# untitled_front4.net
KiCad netlist of a schematic drawn in EAGLE
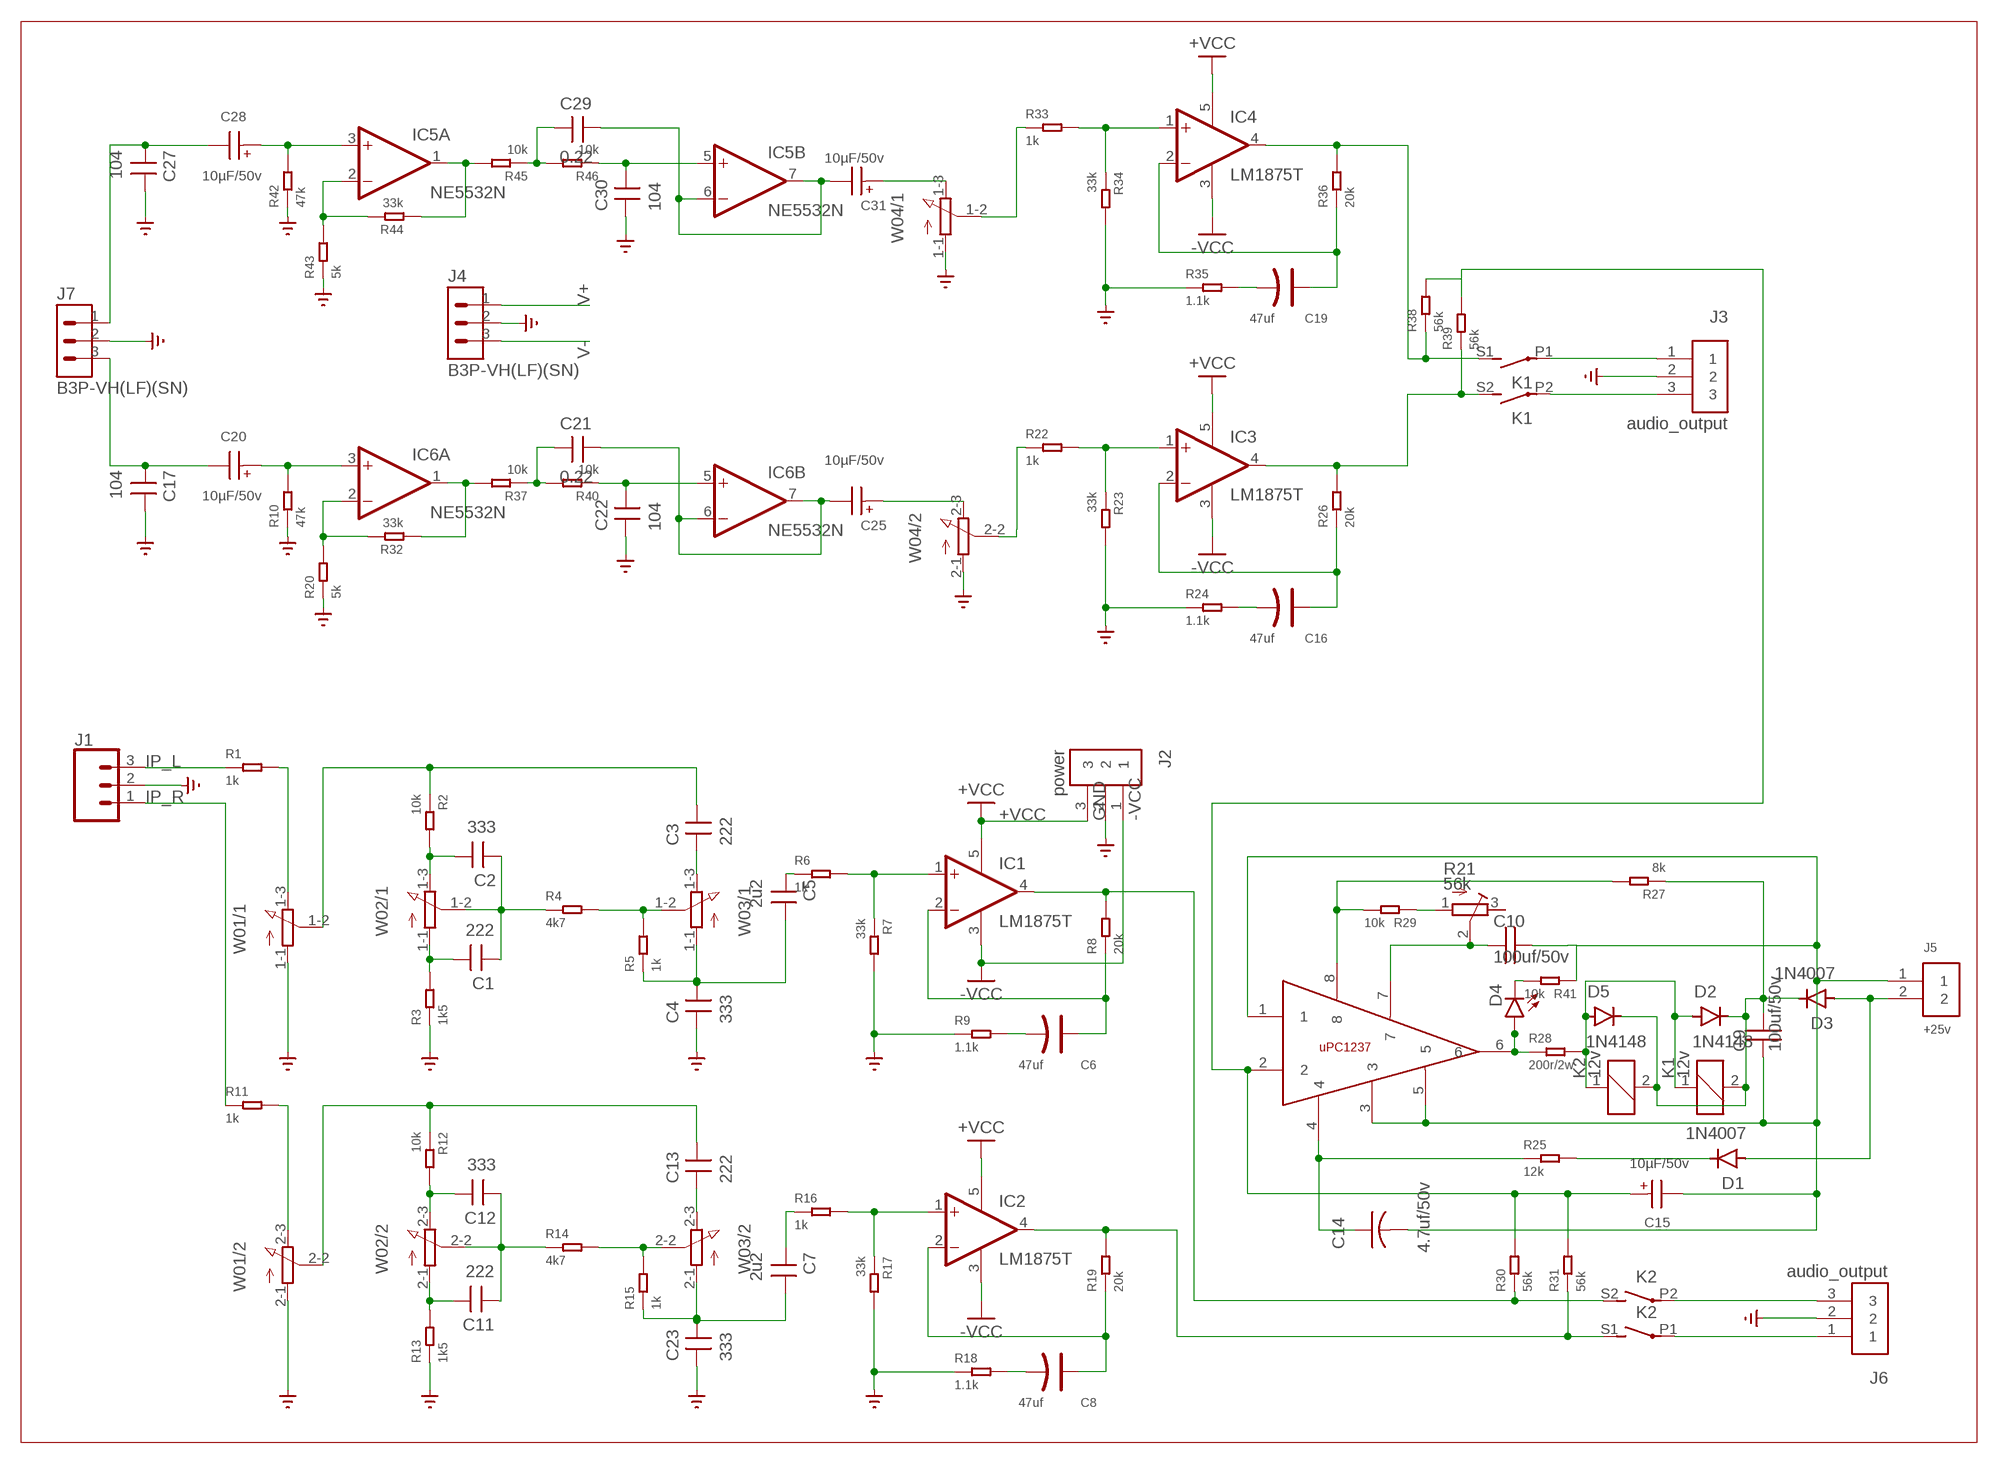
[diagram p0: schematic, sheet 1]

(export (version "E")
  (design (tool "Eeschema 10.0.6"))
  (components
    (comp (ref "C1")
      (value "222")
      (footprint "eagle-import:5.08MM-独石电容")
      (libsource (lib "eagle-import") (part "5.08MM-"))
    )
    (comp (ref "C2")
      (value "333")
      (footprint "eagle-import:5.08MM-独石电容")
      (libsource (lib "eagle-import") (part "5.08MM-"))
    )
    (comp (ref "C3")
      (value "222")
      (footprint "eagle-import:5.08MM-独石电容")
      (libsource (lib "eagle-import") (part "5.08MM-"))
    )
    (comp (ref "C4")
      (value "333")
      (footprint "eagle-import:5.08MM-独石电容")
      (libsource (lib "eagle-import") (part "5.08MM-"))
    )
    (comp (ref "C5")
      (value "2u2")
      (footprint "eagle-import:5.08MM-独石电容")
      (libsource (lib "eagle-import") (part "5.08MM-"))
    )
    (comp (ref "C6")
      (value "47uf")
      (footprint "eagle-import:PC-D5.3MM")
      (fields (field (name "MPN") "KS 100uF/16V"))
      (libsource (lib "eagle-import") (part "DIP-ALUMINUM-47UF-16V(D5-H7MM)"))
    )
    (comp (ref "C7")
      (value "2u2")
      (footprint "eagle-import:5.08MM-独石电容")
      (libsource (lib "eagle-import") (part "5.08MM-"))
    )
    (comp (ref "C8")
      (value "47uf")
      (footprint "eagle-import:PC-D5.3MM")
      (fields (field (name "MPN") "KS 100uF/16V"))
      (libsource (lib "eagle-import") (part "DIP-ALUMINUM-47UF-16V(D5-H7MM)"))
    )
    (comp (ref "C9")
      (value "100uf/50v")
      (footprint "eagle-import:8X12")
      (libsource (lib "eagle-import") (part "50V100UF8X12"))
    )
    (comp (ref "C10")
      (value "100uf/50v")
      (footprint "eagle-import:8X12")
      (libsource (lib "eagle-import") (part "50V100UF8X12"))
    )
    (comp (ref "C11")
      (value "222")
      (footprint "eagle-import:5.08MM-独石电容")
      (libsource (lib "eagle-import") (part "5.08MM-"))
    )
    (comp (ref "C12")
      (value "333")
      (footprint "eagle-import:5.08MM-独石电容")
      (libsource (lib "eagle-import") (part "5.08MM-"))
    )
    (comp (ref "C13")
      (value "222")
      (footprint "eagle-import:5.08MM-独石电容")
      (libsource (lib "eagle-import") (part "5.08MM-"))
    )
    (comp (ref "C14")
      (value "4.7uf/50v")
      (footprint "eagle-import:CAP_RADIAL_2MM")
      (fields
        (field (name "DIGIKEY_PART_NUMBER") "P5175-ND")
        (field (name "MANUFACTURER") "Panasonic Electronic Components")
        (field (name "MPN") "ECA-1HM2R2")
        (field (name "CREATED_BY") "PCBLayout.com")
      )
      (libsource (lib "eagle-import") (part "ECA-1HM2R2"))
    )
    (comp (ref "C15")
      (value "10µF/50v")
      (footprint "eagle-import:WCAP-AT1H_5X11(DXL)")
      (libsource (lib "eagle-import") (part "WCAP-AT1H_5X11_860240272001"))
    )
    (comp (ref "C16")
      (value "47uf")
      (footprint "eagle-import:PC-D5.3MM")
      (fields (field (name "MPN") "KS 100uF/16V"))
      (libsource (lib "eagle-import") (part "DIP-ALUMINUM-47UF-16V(D5-H7MM)"))
    )
    (comp (ref "C17")
      (value "104")
      (footprint "eagle-import:5.08MM-独石电容")
      (libsource (lib "eagle-import") (part "5.08MM-"))
    )
    (comp (ref "C19")
      (value "47uf")
      (footprint "eagle-import:PC-D5.3MM")
      (fields (field (name "MPN") "KS 100uF/16V"))
      (libsource (lib "eagle-import") (part "DIP-ALUMINUM-47UF-16V(D5-H7MM)"))
    )
    (comp (ref "C20")
      (value "10µF/50v")
      (footprint "eagle-import:WCAP-AT1H_5X11(DXL)")
      (libsource (lib "eagle-import") (part "WCAP-AT1H_5X11_860240272001"))
    )
    (comp (ref "C21")
      (value "0.22")
      (footprint "eagle-import:5.08MM-独石电容")
      (libsource (lib "eagle-import") (part "5.08MM-"))
    )
    (comp (ref "C22")
      (value "104")
      (footprint "eagle-import:5.08MM-独石电容")
      (libsource (lib "eagle-import") (part "5.08MM-"))
    )
    (comp (ref "C23")
      (value "333")
      (footprint "eagle-import:5.08MM-独石电容")
      (libsource (lib "eagle-import") (part "5.08MM-"))
    )
    (comp (ref "C25")
      (value "10µF/50v")
      (footprint "eagle-import:WCAP-AT1H_5X11(DXL)")
      (libsource (lib "eagle-import") (part "WCAP-AT1H_5X11_860240272001"))
    )
    (comp (ref "C27")
      (value "104")
      (footprint "eagle-import:5.08MM-独石电容")
      (libsource (lib "eagle-import") (part "5.08MM-"))
    )
    (comp (ref "C28")
      (value "10µF/50v")
      (footprint "eagle-import:WCAP-AT1H_5X11(DXL)")
      (libsource (lib "eagle-import") (part "WCAP-AT1H_5X11_860240272001"))
    )
    (comp (ref "C29")
      (value "0.22")
      (footprint "eagle-import:5.08MM-独石电容")
      (libsource (lib "eagle-import") (part "5.08MM-"))
    )
    (comp (ref "C30")
      (value "104")
      (footprint "eagle-import:5.08MM-独石电容")
      (libsource (lib "eagle-import") (part "5.08MM-"))
    )
    (comp (ref "C31")
      (value "10µF/50v")
      (footprint "eagle-import:WCAP-AT1H_5X11(DXL)")
      (libsource (lib "eagle-import") (part "WCAP-AT1H_5X11_860240272001"))
    )
    (comp (ref "D1")
      (value "1N4007")
      (footprint "eagle-import:DO-41")
      (fields
        (field (name "DIGIKEY_PART_NUMBER") "1N4007MSCT-ND")
        (field (name "MANUFACTURER") "Micro Commercial Co")
        (field (name "CREATED_BY") "PCBLayout.com")
      )
      (libsource (lib "eagle-import") (part "1N4007"))
    )
    (comp (ref "D2")
      (value "1N4148")
      (footprint "eagle-import:DO-41")
      (fields
        (field (name "DIGIKEY_PART_NUMBER") "1N4007MSCT-ND")
        (field (name "MANUFACTURER") "Micro Commercial Co")
        (field (name "MPN") "1N4007")
        (field (name "CREATED_BY") "PCBLayout.com")
      )
      (libsource (lib "eagle-import") (part "1N4007"))
    )
    (comp (ref "D3")
      (value "1N4007")
      (footprint "eagle-import:DO-41")
      (fields
        (field (name "DIGIKEY_PART_NUMBER") "1N4007MSCT-ND")
        (field (name "MANUFACTURER") "Micro Commercial Co")
        (field (name "CREATED_BY") "PCBLayout.com")
      )
      (libsource (lib "eagle-import") (part "1N4007"))
    )
    (comp (ref "D4")
      (value "BEAGLEBONE_BLUE_LED-3MM-NO_SILK")
      (footprint "eagle-import:BEAGLEBONE_BLUE_BEAGLEBONE_BLUE_LED3MM-NS")
      (libsource (lib "eagle-import") (part "BEAGLEBONE_BLUE_LED-3MM-NO_SILK"))
    )
    (comp (ref "D5")
      (value "1N4148")
      (footprint "eagle-import:DO-41")
      (fields
        (field (name "DIGIKEY_PART_NUMBER") "1N4007MSCT-ND")
        (field (name "MANUFACTURER") "Micro Commercial Co")
        (field (name "MPN") "1N4007")
        (field (name "CREATED_BY") "PCBLayout.com")
      )
      (libsource (lib "eagle-import") (part "1N4007"))
    )
    (comp (ref "IC1")
      (value "LM1875T")
      (footprint "eagle-import:CB367")
      (libsource (lib "eagle-import") (part "LM1875T"))
    )
    (comp (ref "IC2")
      (value "LM1875T")
      (footprint "eagle-import:CB367")
      (libsource (lib "eagle-import") (part "LM1875T"))
    )
    (comp (ref "IC3")
      (value "LM1875T")
      (footprint "eagle-import:CB367")
      (libsource (lib "eagle-import") (part "LM1875T"))
    )
    (comp (ref "IC4")
      (value "LM1875T")
      (footprint "eagle-import:CB367")
      (libsource (lib "eagle-import") (part "LM1875T"))
    )
    (comp (ref "IC5")
      (value "NE5532N")
      (footprint "eagle-import:DIL08")
      (libsource (lib "eagle-import") (part "NE5532N"))
    )
    (comp (ref "IC6")
      (value "NE5532N")
      (footprint "eagle-import:DIL08")
      (libsource (lib "eagle-import") (part "NE5532N"))
    )
    (comp (ref "J1")
      (value "CONN_03POLAR")
      (footprint "eagle-import:MOLEX-1X3")
      (libsource (lib "eagle-import") (part "CONN_03POLAR"))
    )
    (comp (ref "J2")
      (value "power")
      (footprint "eagle-import:TERMINALBLOCK_PLUGGABLE-3-7.62MM")
      (fields
        (field (name "DIGIKEY_PART_NO") "732-2824-ND")
        (field (name "MANUFACTURER") "WURTH ELEKTRONIK")
        (field (name "MPN") "691311400103")
        (field (name "CREATED_BY") "PCBLayout.com")
      )
      (libsource (lib "eagle-import") (part "691311400103"))
    )
    (comp (ref "J3")
      (value "audio_output")
      (footprint "eagle-import:TERMINALBLOCK_PLUGGABLE-3-7.62MM")
      (fields
        (field (name "DIGIKEY_PART_NO") "732-2824-ND")
        (field (name "MANUFACTURER") "WURTH ELEKTRONIK")
        (field (name "MPN") "691311400103")
        (field (name "CREATED_BY") "PCBLayout.com")
      )
      (libsource (lib "eagle-import") (part "691311400103"))
    )
    (comp (ref "J4")
      (value "B3P-VH(LF)(SN)")
      (footprint "eagle-import:HDR-03")
      (fields
        (field (name "DIGIKEY_PART_NUMBER") "455-1640-ND")
        (field (name "MANUFACTURER") "JST Sales America Inc.")
        (field (name "CREATED_BY") "PCBLayout.com")
      )
      (libsource (lib "eagle-import") (part "B3P-VH(LF)(SN)"))
    )
    (comp (ref "J5")
      (value "+25v")
      (footprint "eagle-import:S2B-PH-K-S(LF)(SN)")
      (fields
        (field (name "DIGI_KEY_PART_NUMBER") "455-1719-ND")
        (field (name "MANUFACTURER") "JST Sales America Inc.")
        (field (name "MPN") "S2B-PH-K-S(LF)(SN)")
        (field (name "CREATED_BY") "PCBLayout.com")
      )
      (libsource (lib "eagle-import") (part "S2B-PH-K-S(LF)(SN)"))
    )
    (comp (ref "J6")
      (value "audio_output")
      (footprint "eagle-import:TERMINALBLOCK_PLUGGABLE-3-7.62MM")
      (fields
        (field (name "DIGIKEY_PART_NO") "732-2824-ND")
        (field (name "MANUFACTURER") "WURTH ELEKTRONIK")
        (field (name "MPN") "691311400103")
        (field (name "CREATED_BY") "PCBLayout.com")
      )
      (libsource (lib "eagle-import") (part "691311400103"))
    )
    (comp (ref "J7")
      (value "B3P-VH(LF)(SN)")
      (footprint "eagle-import:HDR-03")
      (fields
        (field (name "DIGIKEY_PART_NUMBER") "455-1640-ND")
        (field (name "MANUFACTURER") "JST Sales America Inc.")
        (field (name "CREATED_BY") "PCBLayout.com")
      )
      (libsource (lib "eagle-import") (part "B3P-VH(LF)(SN)"))
    )
    (comp (ref "K1")
      (value "12v")
      (footprint "eagle-import:G2R2A")
      (fields (field (name "MPN") "G2R-2A-DC24"))
      (libsource (lib "eagle-import") (part "G2R2A"))
    )
    (comp (ref "K2")
      (value "12v")
      (footprint "eagle-import:G2R2A")
      (fields (field (name "MPN") "G2R-2A-DC24"))
      (libsource (lib "eagle-import") (part "G2R2A"))
    )
    (comp (ref "R1")
      (value "1k")
      (footprint "eagle-import:PR-D2.3XL6.5MM")
      (fields (field (name "MPN") "FHCFR-1/4W-105J"))
      (libsource (lib "eagle-import") (part "DIP-RES-1M-5%-1/4W(PR-D2.3XL6.5MM)"))
    )
    (comp (ref "R2")
      (value "10k")
      (footprint "eagle-import:PR-D2.3XL6.5MM")
      (fields (field (name "MPN") "FHCFR-1/4W-105J"))
      (libsource (lib "eagle-import") (part "DIP-RES-1M-5%-1/4W(PR-D2.3XL6.5MM)"))
    )
    (comp (ref "R3")
      (value "1k5")
      (footprint "eagle-import:PR-D2.3XL6.5MM")
      (fields (field (name "MPN") "FHCFR-1/4W-105J"))
      (libsource (lib "eagle-import") (part "DIP-RES-1M-5%-1/4W(PR-D2.3XL6.5MM)"))
    )
    (comp (ref "R4")
      (value "4k7")
      (footprint "eagle-import:PR-D2.3XL6.5MM")
      (fields (field (name "MPN") "FHCFR-1/4W-105J"))
      (libsource (lib "eagle-import") (part "DIP-RES-1M-5%-1/4W(PR-D2.3XL6.5MM)"))
    )
    (comp (ref "R5")
      (value "1k")
      (footprint "eagle-import:PR-D2.3XL6.5MM")
      (fields (field (name "MPN") "FHCFR-1/4W-105J"))
      (libsource (lib "eagle-import") (part "DIP-RES-1M-5%-1/4W(PR-D2.3XL6.5MM)"))
    )
    (comp (ref "R6")
      (value "1k")
      (footprint "eagle-import:PR-D2.3XL6.5MM")
      (fields (field (name "MPN") "FHCFR-1/4W-105J"))
      (libsource (lib "eagle-import") (part "DIP-RES-1M-5%-1/4W(PR-D2.3XL6.5MM)"))
    )
    (comp (ref "R7")
      (value "33k")
      (footprint "eagle-import:PR-D2.3XL6.5MM")
      (fields (field (name "MPN") "FHCFR-1/4W-105J"))
      (libsource (lib "eagle-import") (part "DIP-RES-1M-5%-1/4W(PR-D2.3XL6.5MM)"))
    )
    (comp (ref "R8")
      (value "20k")
      (footprint "eagle-import:PR-D2.3XL6.5MM")
      (fields (field (name "MPN") "FHCFR-1/4W-105J"))
      (libsource (lib "eagle-import") (part "DIP-RES-1M-5%-1/4W(PR-D2.3XL6.5MM)"))
    )
    (comp (ref "R9")
      (value "1.1k")
      (footprint "eagle-import:PR-D2.3XL6.5MM")
      (fields (field (name "MPN") "FHCFR-1/4W-105J"))
      (libsource (lib "eagle-import") (part "DIP-RES-1M-5%-1/4W(PR-D2.3XL6.5MM)"))
    )
    (comp (ref "R10")
      (value "47k")
      (footprint "eagle-import:PR-D2.3XL6.5MM")
      (fields (field (name "MPN") "FHCFR-1/4W-105J"))
      (libsource (lib "eagle-import") (part "DIP-RES-1M-5%-1/4W(PR-D2.3XL6.5MM)"))
    )
    (comp (ref "R11")
      (value "1k")
      (footprint "eagle-import:PR-D2.3XL6.5MM")
      (fields (field (name "MPN") "FHCFR-1/4W-105J"))
      (libsource (lib "eagle-import") (part "DIP-RES-1M-5%-1/4W(PR-D2.3XL6.5MM)"))
    )
    (comp (ref "R12")
      (value "10k")
      (footprint "eagle-import:PR-D2.3XL6.5MM")
      (fields (field (name "MPN") "FHCFR-1/4W-105J"))
      (libsource (lib "eagle-import") (part "DIP-RES-1M-5%-1/4W(PR-D2.3XL6.5MM)"))
    )
    (comp (ref "R13")
      (value "1k5")
      (footprint "eagle-import:PR-D2.3XL6.5MM")
      (fields (field (name "MPN") "FHCFR-1/4W-105J"))
      (libsource (lib "eagle-import") (part "DIP-RES-1M-5%-1/4W(PR-D2.3XL6.5MM)"))
    )
    (comp (ref "R14")
      (value "4k7")
      (footprint "eagle-import:PR-D2.3XL6.5MM")
      (fields (field (name "MPN") "FHCFR-1/4W-105J"))
      (libsource (lib "eagle-import") (part "DIP-RES-1M-5%-1/4W(PR-D2.3XL6.5MM)"))
    )
    (comp (ref "R15")
      (value "1k")
      (footprint "eagle-import:PR-D2.3XL6.5MM")
      (fields (field (name "MPN") "FHCFR-1/4W-105J"))
      (libsource (lib "eagle-import") (part "DIP-RES-1M-5%-1/4W(PR-D2.3XL6.5MM)"))
    )
    (comp (ref "R16")
      (value "1k")
      (footprint "eagle-import:PR-D2.3XL6.5MM")
      (fields (field (name "MPN") "FHCFR-1/4W-105J"))
      (libsource (lib "eagle-import") (part "DIP-RES-1M-5%-1/4W(PR-D2.3XL6.5MM)"))
    )
    (comp (ref "R17")
      (value "33k")
      (footprint "eagle-import:PR-D2.3XL6.5MM")
      (fields (field (name "MPN") "FHCFR-1/4W-105J"))
      (libsource (lib "eagle-import") (part "DIP-RES-1M-5%-1/4W(PR-D2.3XL6.5MM)"))
    )
    (comp (ref "R18")
      (value "1.1k")
      (footprint "eagle-import:PR-D2.3XL6.5MM")
      (fields (field (name "MPN") "FHCFR-1/4W-105J"))
      (libsource (lib "eagle-import") (part "DIP-RES-1M-5%-1/4W(PR-D2.3XL6.5MM)"))
    )
    (comp (ref "R19")
      (value "20k")
      (footprint "eagle-import:PR-D2.3XL6.5MM")
      (fields (field (name "MPN") "FHCFR-1/4W-105J"))
      (libsource (lib "eagle-import") (part "DIP-RES-1M-5%-1/4W(PR-D2.3XL6.5MM)"))
    )
    (comp (ref "R20")
      (value "5k")
      (footprint "eagle-import:PR-D2.3XL6.5MM")
      (fields (field (name "MPN") "FHCFR-1/4W-105J"))
      (libsource (lib "eagle-import") (part "DIP-RES-1M-5%-1/4W(PR-D2.3XL6.5MM)"))
    )
    (comp (ref "R21")
      (value "56k")
      (footprint "eagle-import:RTRIM3296W")
      (libsource (lib "eagle-import") (part "R-TRIMM3296W"))
    )
    (comp (ref "R22")
      (value "1k")
      (footprint "eagle-import:PR-D2.3XL6.5MM")
      (fields (field (name "MPN") "FHCFR-1/4W-105J"))
      (libsource (lib "eagle-import") (part "DIP-RES-1M-5%-1/4W(PR-D2.3XL6.5MM)"))
    )
    (comp (ref "R23")
      (value "33k")
      (footprint "eagle-import:PR-D2.3XL6.5MM")
      (fields (field (name "MPN") "FHCFR-1/4W-105J"))
      (libsource (lib "eagle-import") (part "DIP-RES-1M-5%-1/4W(PR-D2.3XL6.5MM)"))
    )
    (comp (ref "R24")
      (value "1.1k")
      (footprint "eagle-import:PR-D2.3XL6.5MM")
      (fields (field (name "MPN") "FHCFR-1/4W-105J"))
      (libsource (lib "eagle-import") (part "DIP-RES-1M-5%-1/4W(PR-D2.3XL6.5MM)"))
    )
    (comp (ref "R25")
      (value "12k")
      (footprint "eagle-import:PR-D2.3XL6.5MM")
      (fields (field (name "MPN") "FHCFR-1/4W-105J"))
      (libsource (lib "eagle-import") (part "DIP-RES-1M-5%-1/4W(PR-D2.3XL6.5MM)"))
    )
    (comp (ref "R26")
      (value "20k")
      (footprint "eagle-import:PR-D2.3XL6.5MM")
      (fields (field (name "MPN") "FHCFR-1/4W-105J"))
      (libsource (lib "eagle-import") (part "DIP-RES-1M-5%-1/4W(PR-D2.3XL6.5MM)"))
    )
    (comp (ref "R27")
      (value "8k")
      (footprint "eagle-import:PR-D2.3XL6.5MM")
      (fields (field (name "MPN") "FHCFR-1/4W-105J"))
      (libsource (lib "eagle-import") (part "DIP-RES-1M-5%-1/4W(PR-D2.3XL6.5MM)"))
    )
    (comp (ref "R28")
      (value "200r/2w")
      (footprint "eagle-import:PR-D2.3XL6.5MM")
      (fields (field (name "MPN") "FHCFR-1/4W-105J"))
      (libsource (lib "eagle-import") (part "DIP-RES-1M-5%-1/4W(PR-D2.3XL6.5MM)"))
    )
    (comp (ref "R29")
      (value "10k")
      (footprint "eagle-import:PR-D2.3XL6.5MM")
      (fields (field (name "MPN") "FHCFR-1/4W-105J"))
      (libsource (lib "eagle-import") (part "DIP-RES-1M-5%-1/4W(PR-D2.3XL6.5MM)"))
    )
    (comp (ref "R30")
      (value "56k")
      (footprint "eagle-import:PR-D2.3XL6.5MM")
      (fields (field (name "MPN") "FHCFR-1/4W-105J"))
      (libsource (lib "eagle-import") (part "DIP-RES-1M-5%-1/4W(PR-D2.3XL6.5MM)"))
    )
    (comp (ref "R31")
      (value "56k")
      (footprint "eagle-import:PR-D2.3XL6.5MM")
      (fields (field (name "MPN") "FHCFR-1/4W-105J"))
      (libsource (lib "eagle-import") (part "DIP-RES-1M-5%-1/4W(PR-D2.3XL6.5MM)"))
    )
    (comp (ref "R32")
      (value "33k")
      (footprint "eagle-import:PR-D2.3XL6.5MM")
      (fields (field (name "MPN") "FHCFR-1/4W-105J"))
      (libsource (lib "eagle-import") (part "DIP-RES-1M-5%-1/4W(PR-D2.3XL6.5MM)"))
    )
    (comp (ref "R33")
      (value "1k")
      (footprint "eagle-import:PR-D2.3XL6.5MM")
      (fields (field (name "MPN") "FHCFR-1/4W-105J"))
      (libsource (lib "eagle-import") (part "DIP-RES-1M-5%-1/4W(PR-D2.3XL6.5MM)"))
    )
    (comp (ref "R34")
      (value "33k")
      (footprint "eagle-import:PR-D2.3XL6.5MM")
      (fields (field (name "MPN") "FHCFR-1/4W-105J"))
      (libsource (lib "eagle-import") (part "DIP-RES-1M-5%-1/4W(PR-D2.3XL6.5MM)"))
    )
    (comp (ref "R35")
      (value "1.1k")
      (footprint "eagle-import:PR-D2.3XL6.5MM")
      (fields (field (name "MPN") "FHCFR-1/4W-105J"))
      (libsource (lib "eagle-import") (part "DIP-RES-1M-5%-1/4W(PR-D2.3XL6.5MM)"))
    )
    (comp (ref "R36")
      (value "20k")
      (footprint "eagle-import:PR-D2.3XL6.5MM")
      (fields (field (name "MPN") "FHCFR-1/4W-105J"))
      (libsource (lib "eagle-import") (part "DIP-RES-1M-5%-1/4W(PR-D2.3XL6.5MM)"))
    )
    (comp (ref "R37")
      (value "10k")
      (footprint "eagle-import:PR-D2.3XL6.5MM")
      (fields (field (name "MPN") "FHCFR-1/4W-105J"))
      (libsource (lib "eagle-import") (part "DIP-RES-1M-5%-1/4W(PR-D2.3XL6.5MM)"))
    )
    (comp (ref "R38")
      (value "56k")
      (footprint "eagle-import:PR-D2.3XL6.5MM")
      (fields (field (name "MPN") "FHCFR-1/4W-105J"))
      (libsource (lib "eagle-import") (part "DIP-RES-1M-5%-1/4W(PR-D2.3XL6.5MM)"))
    )
    (comp (ref "R39")
      (value "56k")
      (footprint "eagle-import:PR-D2.3XL6.5MM")
      (fields (field (name "MPN") "FHCFR-1/4W-105J"))
      (libsource (lib "eagle-import") (part "DIP-RES-1M-5%-1/4W(PR-D2.3XL6.5MM)"))
    )
    (comp (ref "R40")
      (value "10k")
      (footprint "eagle-import:PR-D2.3XL6.5MM")
      (fields (field (name "MPN") "FHCFR-1/4W-105J"))
      (libsource (lib "eagle-import") (part "DIP-RES-1M-5%-1/4W(PR-D2.3XL6.5MM)"))
    )
    (comp (ref "R41")
      (value "10k")
      (footprint "eagle-import:PR-D2.3XL6.5MM")
      (fields (field (name "MPN") "FHCFR-1/4W-105J"))
      (libsource (lib "eagle-import") (part "DIP-RES-1M-5%-1/4W(PR-D2.3XL6.5MM)"))
    )
    (comp (ref "R42")
      (value "47k")
      (footprint "eagle-import:PR-D2.3XL6.5MM")
      (fields (field (name "MPN") "FHCFR-1/4W-105J"))
      (libsource (lib "eagle-import") (part "DIP-RES-1M-5%-1/4W(PR-D2.3XL6.5MM)"))
    )
    (comp (ref "R43")
      (value "5k")
      (footprint "eagle-import:PR-D2.3XL6.5MM")
      (fields (field (name "MPN") "FHCFR-1/4W-105J"))
      (libsource (lib "eagle-import") (part "DIP-RES-1M-5%-1/4W(PR-D2.3XL6.5MM)"))
    )
    (comp (ref "R44")
      (value "33k")
      (footprint "eagle-import:PR-D2.3XL6.5MM")
      (fields (field (name "MPN") "FHCFR-1/4W-105J"))
      (libsource (lib "eagle-import") (part "DIP-RES-1M-5%-1/4W(PR-D2.3XL6.5MM)"))
    )
    (comp (ref "R45")
      (value "10k")
      (footprint "eagle-import:PR-D2.3XL6.5MM")
      (fields (field (name "MPN") "FHCFR-1/4W-105J"))
      (libsource (lib "eagle-import") (part "DIP-RES-1M-5%-1/4W(PR-D2.3XL6.5MM)"))
    )
    (comp (ref "R46")
      (value "10k")
      (footprint "eagle-import:PR-D2.3XL6.5MM")
      (fields (field (name "MPN") "FHCFR-1/4W-105J"))
      (libsource (lib "eagle-import") (part "DIP-RES-1M-5%-1/4W(PR-D2.3XL6.5MM)"))
    )
    (comp (ref "U2")
      (value "UPC1237HA")
      (footprint "eagle-import:SIP8")
      (libsource (lib "eagle-import") (part "UPC1237HA"))
    )
    (comp (ref "W01")
      (value "3RP/1610G")
      (footprint "eagle-import:3RP_1610G")
      (libsource (lib "eagle-import") (part "3RP/1610G"))
    )
    (comp (ref "W02")
      (value "3RP/1610G")
      (footprint "eagle-import:3RP_1610G")
      (libsource (lib "eagle-import") (part "3RP/1610G"))
    )
    (comp (ref "W03")
      (value "3RP/1610G")
      (footprint "eagle-import:3RP_1610G")
      (libsource (lib "eagle-import") (part "3RP/1610G"))
    )
    (comp (ref "W04")
      (value "3RP/1610G")
      (footprint "eagle-import:3RP_1610G")
      (libsource (lib "eagle-import") (part "3RP/1610G"))
    )
  )
  (nets
    (net (code "1") (name "+VCC") (class "Default")
      (node (ref "IC1") (pin "5") (pinfunction "V+_5") (pintype "power_in"))
      (node (ref "IC2") (pin "5") (pinfunction "V+_5") (pintype "power_in"))
      (node (ref "IC3") (pin "5") (pinfunction "V+_5") (pintype "power_in"))
      (node (ref "IC4") (pin "5") (pinfunction "V+_5") (pintype "power_in"))
      (node (ref "J2") (pin "3") (pinfunction "3_3") (pintype "passive"))
    )
    (net (code "2") (name "-VCC") (class "Default")
      (node (ref "IC1") (pin "3") (pinfunction "V-_3") (pintype "power_in"))
      (node (ref "IC2") (pin "3") (pinfunction "V-_3") (pintype "power_in"))
      (node (ref "IC3") (pin "3") (pinfunction "V-_3") (pintype "power_in"))
      (node (ref "IC4") (pin "3") (pinfunction "V-_3") (pintype "power_in"))
      (node (ref "J2") (pin "1") (pinfunction "1_1") (pintype "passive"))
    )
    (net (code "3") (name "/IP_L") (class "Default")
      (node (ref "J1") (pin "3") (pinfunction "3_3") (pintype "passive"))
      (node (ref "R1") (pin "1") (pinfunction "1_1") (pintype "passive"))
    )
    (net (code "4") (name "/IP_R") (class "Default")
      (node (ref "J1") (pin "1") (pinfunction "1_1") (pintype "passive"))
      (node (ref "R11") (pin "1") (pinfunction "1_1") (pintype "passive"))
    )
    (net (code "5") (name "/V+") (class "Default")
      (node (ref "J4") (pin "1") (pinfunction "1_1") (pintype "passive"))
    )
    (net (code "6") (name "/V-") (class "Default")
      (node (ref "J4") (pin "3") (pinfunction "3_3") (pintype "passive"))
    )
    (net (code "7") (name "Net-(C1-1)") (class "Default")
      (node (ref "C1") (pin "P$2") (pinfunction "1_P$2") (pintype "bidirectional"))
      (node (ref "C2") (pin "P$2") (pinfunction "1_P$2") (pintype "bidirectional"))
      (node (ref "R4") (pin "1") (pinfunction "1_1") (pintype "passive"))
      (node (ref "W02") (pin "1-2") (pinfunction "S_1-2") (pintype "passive"))
    )
    (net (code "8") (name "Net-(C1-2)") (class "Default")
      (node (ref "C1") (pin "P$1") (pinfunction "2_P$1") (pintype "bidirectional"))
      (node (ref "R3") (pin "2") (pinfunction "2_2") (pintype "passive"))
      (node (ref "W02") (pin "1-1") (pinfunction "A_1-1") (pintype "passive"))
    )
    (net (code "9") (name "Net-(C2-2)") (class "Default")
      (node (ref "C2") (pin "P$1") (pinfunction "2_P$1") (pintype "bidirectional"))
      (node (ref "R2") (pin "2") (pinfunction "2_2") (pintype "passive"))
      (node (ref "W02") (pin "1-3") (pinfunction "E_1-3") (pintype "passive"))
    )
    (net (code "10") (name "Net-(C3-1)") (class "Default")
      (node (ref "C3") (pin "P$2") (pinfunction "1_P$2") (pintype "bidirectional"))
      (node (ref "W03") (pin "1-3") (pinfunction "E_1-3") (pintype "passive"))
    )
    (net (code "11") (name "Net-(C3-2)") (class "Default")
      (node (ref "C3") (pin "P$1") (pinfunction "2_P$1") (pintype "bidirectional"))
      (node (ref "R2") (pin "1") (pinfunction "1_1") (pintype "passive"))
      (node (ref "W01") (pin "1-2") (pinfunction "S_1-2") (pintype "passive"))
    )
    (net (code "12") (name "Net-(C4-2)") (class "Default")
      (node (ref "C4") (pin "P$1") (pinfunction "2_P$1") (pintype "bidirectional"))
      (node (ref "C5") (pin "P$1") (pinfunction "2_P$1") (pintype "bidirectional"))
      (node (ref "R5") (pin "1") (pinfunction "1_1") (pintype "passive"))
      (node (ref "W03") (pin "1-1") (pinfunction "A_1-1") (pintype "passive"))
    )
    (net (code "13") (name "Net-(C5-1)") (class "Default")
      (node (ref "C5") (pin "P$2") (pinfunction "1_P$2") (pintype "bidirectional"))
      (node (ref "R6") (pin "1") (pinfunction "1_1") (pintype "passive"))
    )
    (net (code "14") (name "Net-(C6-Pad-)") (class "Default")
      (node (ref "C6") (pin "-") (pinfunction "-_-") (pintype "passive"))
      (node (ref "R9") (pin "2") (pinfunction "2_2") (pintype "passive"))
    )
    (net (code "15") (name "Net-(C7-1)") (class "Default")
      (node (ref "C7") (pin "P$2") (pinfunction "1_P$2") (pintype "bidirectional"))
      (node (ref "R16") (pin "1") (pinfunction "1_1") (pintype "passive"))
    )
    (net (code "16") (name "Net-(C8-Pad-)") (class "Default")
      (node (ref "C8") (pin "-") (pinfunction "-_-") (pintype "passive"))
      (node (ref "R18") (pin "2") (pinfunction "2_2") (pintype "passive"))
    )
    (net (code "17") (name "Net-(C9-Pad2)") (class "Default")
      (node (ref "C9") (pin "2") (pinfunction "2_2") (pintype "bidirectional"))
      (node (ref "D2") (pin "C") (pinfunction "C_C") (pintype "passive"))
      (node (ref "D3") (pin "C") (pinfunction "C_C") (pintype "passive"))
      (node (ref "D5") (pin "C") (pinfunction "C_C") (pintype "passive"))
      (node (ref "K1") (pin "2") (pinfunction "2_2") (pintype "passive"))
      (node (ref "K2") (pin "2") (pinfunction "2_2") (pintype "passive"))
      (node (ref "R27") (pin "1") (pinfunction "1_1") (pintype "passive"))
    )
    (net (code "18") (name "Net-(C11-1)") (class "Default")
      (node (ref "C11") (pin "P$2") (pinfunction "1_P$2") (pintype "bidirectional"))
      (node (ref "C12") (pin "P$2") (pinfunction "1_P$2") (pintype "bidirectional"))
      (node (ref "R14") (pin "1") (pinfunction "1_1") (pintype "passive"))
      (node (ref "W02") (pin "2-2") (pinfunction "S_2-2") (pintype "passive"))
    )
    (net (code "19") (name "Net-(C11-2)") (class "Default")
      (node (ref "C11") (pin "P$1") (pinfunction "2_P$1") (pintype "bidirectional"))
      (node (ref "R13") (pin "2") (pinfunction "2_2") (pintype "passive"))
      (node (ref "W02") (pin "2-1") (pinfunction "A_2-1") (pintype "passive"))
    )
    (net (code "20") (name "Net-(C12-2)") (class "Default")
      (node (ref "C12") (pin "P$1") (pinfunction "2_P$1") (pintype "bidirectional"))
      (node (ref "R12") (pin "2") (pinfunction "2_2") (pintype "passive"))
      (node (ref "W02") (pin "2-3") (pinfunction "E_2-3") (pintype "passive"))
    )
    (net (code "21") (name "Net-(C13-1)") (class "Default")
      (node (ref "C13") (pin "P$2") (pinfunction "1_P$2") (pintype "bidirectional"))
      (node (ref "W03") (pin "2-3") (pinfunction "E_2-3") (pintype "passive"))
    )
    (net (code "22") (name "Net-(C13-2)") (class "Default")
      (node (ref "C13") (pin "P$1") (pinfunction "2_P$1") (pintype "bidirectional"))
      (node (ref "R12") (pin "1") (pinfunction "1_1") (pintype "passive"))
      (node (ref "W01") (pin "2-2") (pinfunction "S_2-2") (pintype "passive"))
    )
    (net (code "23") (name "Net-(C14-Pad1)") (class "Default")
      (node (ref "C14") (pin "1") (pinfunction "1_1") (pintype "passive"))
      (node (ref "R25") (pin "1") (pinfunction "1_1") (pintype "passive"))
      (node (ref "U2") (pin "4") (pinfunction "4_4") (pintype "bidirectional"))
    )
    (net (code "24") (name "Net-(C15-+)") (class "Default")
      (node (ref "C15") (pin "1") (pinfunction "+_1") (pintype "passive"))
      (node (ref "R30") (pin "2") (pinfunction "2_2") (pintype "passive"))
      (node (ref "R31") (pin "2") (pinfunction "2_2") (pintype "passive"))
      (node (ref "R38") (pin "2") (pinfunction "2_2") (pintype "passive"))
      (node (ref "R39") (pin "2") (pinfunction "2_2") (pintype "passive"))
      (node (ref "U2") (pin "2") (pinfunction "2_2") (pintype "bidirectional"))
    )
    (net (code "25") (name "Net-(C15--)") (class "Default")
      (node (ref "C10") (pin "2") (pinfunction "2_2") (pintype "bidirectional"))
      (node (ref "C14") (pin "2") (pinfunction "2_2") (pintype "passive"))
      (node (ref "C15") (pin "2") (pinfunction "-_2") (pintype "passive"))
      (node (ref "C9") (pin "1") (pinfunction "1_1") (pintype "bidirectional"))
      (node (ref "J5") (pin "1") (pinfunction "1_1") (pintype "passive"))
      (node (ref "R41") (pin "1") (pinfunction "1_1") (pintype "passive"))
      (node (ref "U2") (pin "1") (pinfunction "1_1") (pintype "bidirectional"))
      (node (ref "U2") (pin "3") (pinfunction "3_3") (pintype "bidirectional"))
      (node (ref "U2") (pin "5") (pinfunction "5_5") (pintype "bidirectional"))
    )
    (net (code "26") (name "Net-(C16-Pad-)") (class "Default")
      (node (ref "C16") (pin "-") (pinfunction "-_-") (pintype "passive"))
      (node (ref "R24") (pin "2") (pinfunction "2_2") (pintype "passive"))
    )
    (net (code "27") (name "Net-(C17-1)") (class "Default")
      (node (ref "C17") (pin "P$2") (pinfunction "1_P$2") (pintype "bidirectional"))
      (node (ref "C20") (pin "2") (pinfunction "-_2") (pintype "passive"))
      (node (ref "J7") (pin "3") (pinfunction "3_3") (pintype "passive"))
    )
    (net (code "28") (name "Net-(C19-Pad-)") (class "Default")
      (node (ref "C19") (pin "-") (pinfunction "-_-") (pintype "passive"))
      (node (ref "R35") (pin "2") (pinfunction "2_2") (pintype "passive"))
    )
    (net (code "29") (name "Net-(C20-+)") (class "Default")
      (node (ref "C20") (pin "1") (pinfunction "+_1") (pintype "passive"))
      (node (ref "IC6") (pin "3") (pinfunction "+IN_3") (pintype "input"))
      (node (ref "R10") (pin "2") (pinfunction "2_2") (pintype "passive"))
    )
    (net (code "30") (name "Net-(C21-1)") (class "Default")
      (node (ref "C21") (pin "P$2") (pinfunction "1_P$2") (pintype "bidirectional"))
      (node (ref "R37") (pin "1") (pinfunction "1_1") (pintype "passive"))
      (node (ref "R40") (pin "2") (pinfunction "2_2") (pintype "passive"))
    )
    (net (code "31") (name "Net-(C21-2)") (class "Default")
      (node (ref "C21") (pin "P$1") (pinfunction "2_P$1") (pintype "bidirectional"))
      (node (ref "C25") (pin "2") (pinfunction "-_2") (pintype "passive"))
      (node (ref "IC6") (pin "6") (pinfunction "-IN_6") (pintype "input"))
      (node (ref "IC6") (pin "7") (pinfunction "OUT_7") (pintype "output"))
    )
    (net (code "32") (name "Net-(C22-2)") (class "Default")
      (node (ref "C22") (pin "P$1") (pinfunction "2_P$1") (pintype "bidirectional"))
      (node (ref "IC6") (pin "5") (pinfunction "+IN_5") (pintype "input"))
      (node (ref "R40") (pin "1") (pinfunction "1_1") (pintype "passive"))
    )
    (net (code "33") (name "Net-(C23-2)") (class "Default")
      (node (ref "C23") (pin "P$1") (pinfunction "2_P$1") (pintype "bidirectional"))
      (node (ref "C7") (pin "P$1") (pinfunction "2_P$1") (pintype "bidirectional"))
      (node (ref "R15") (pin "1") (pinfunction "1_1") (pintype "passive"))
      (node (ref "W03") (pin "2-1") (pinfunction "A_2-1") (pintype "passive"))
    )
    (net (code "34") (name "Net-(C25-+)") (class "Default")
      (node (ref "C25") (pin "1") (pinfunction "+_1") (pintype "passive"))
      (node (ref "W04") (pin "2-3") (pinfunction "E_2-3") (pintype "passive"))
    )
    (net (code "35") (name "Net-(C27-1)") (class "Default")
      (node (ref "C27") (pin "P$2") (pinfunction "1_P$2") (pintype "bidirectional"))
      (node (ref "C28") (pin "2") (pinfunction "-_2") (pintype "passive"))
      (node (ref "J7") (pin "1") (pinfunction "1_1") (pintype "passive"))
    )
    (net (code "36") (name "Net-(C28-+)") (class "Default")
      (node (ref "C28") (pin "1") (pinfunction "+_1") (pintype "passive"))
      (node (ref "IC5") (pin "3") (pinfunction "+IN_3") (pintype "input"))
      (node (ref "R42") (pin "2") (pinfunction "2_2") (pintype "passive"))
    )
    (net (code "37") (name "Net-(C29-1)") (class "Default")
      (node (ref "C29") (pin "P$2") (pinfunction "1_P$2") (pintype "bidirectional"))
      (node (ref "R45") (pin "1") (pinfunction "1_1") (pintype "passive"))
      (node (ref "R46") (pin "2") (pinfunction "2_2") (pintype "passive"))
    )
    (net (code "38") (name "Net-(C29-2)") (class "Default")
      (node (ref "C29") (pin "P$1") (pinfunction "2_P$1") (pintype "bidirectional"))
      (node (ref "C31") (pin "2") (pinfunction "-_2") (pintype "passive"))
      (node (ref "IC5") (pin "6") (pinfunction "-IN_6") (pintype "input"))
      (node (ref "IC5") (pin "7") (pinfunction "OUT_7") (pintype "output"))
    )
    (net (code "39") (name "Net-(C30-2)") (class "Default")
      (node (ref "C30") (pin "P$1") (pinfunction "2_P$1") (pintype "bidirectional"))
      (node (ref "IC5") (pin "5") (pinfunction "+IN_5") (pintype "input"))
      (node (ref "R46") (pin "1") (pinfunction "1_1") (pintype "passive"))
    )
    (net (code "40") (name "Net-(C31-+)") (class "Default")
      (node (ref "C31") (pin "1") (pinfunction "+_1") (pintype "passive"))
      (node (ref "W04") (pin "1-3") (pinfunction "E_1-3") (pintype "passive"))
    )
    (net (code "41") (name "Net-(D1-PadA)") (class "Default")
      (node (ref "D1") (pin "A") (pinfunction "A_A") (pintype "passive"))
      (node (ref "D3") (pin "A") (pinfunction "A_A") (pintype "passive"))
      (node (ref "J5") (pin "2") (pinfunction "2_2") (pintype "passive"))
    )
    (net (code "42") (name "Net-(D1-PadC)") (class "Default")
      (node (ref "D1") (pin "C") (pinfunction "C_C") (pintype "passive"))
      (node (ref "R25") (pin "2") (pinfunction "2_2") (pintype "passive"))
    )
    (net (code "43") (name "Net-(D2-PadA)") (class "Default")
      (node (ref "D2") (pin "A") (pinfunction "A_A") (pintype "passive"))
      (node (ref "D5") (pin "A") (pinfunction "A_A") (pintype "passive"))
      (node (ref "K1") (pin "1") (pinfunction "1_1") (pintype "passive"))
      (node (ref "K2") (pin "1") (pinfunction "1_1") (pintype "passive"))
      (node (ref "R28") (pin "2") (pinfunction "2_2") (pintype "passive"))
    )
    (net (code "44") (name "Net-(D4-C)") (class "Default")
      (node (ref "D4") (pin "K") (pinfunction "C_K") (pintype "passive"))
      (node (ref "R41") (pin "2") (pinfunction "2_2") (pintype "passive"))
    )
    (net (code "45") (name "Net-(D4-PadA)") (class "Default")
      (node (ref "D4") (pin "A") (pinfunction "A_A") (pintype "passive"))
      (node (ref "R28") (pin "1") (pinfunction "1_1") (pintype "passive"))
      (node (ref "U2") (pin "6") (pinfunction "6_6") (pintype "bidirectional"))
    )
    (net (code "46") (name "Net-(IC1-+IN)") (class "Default")
      (node (ref "IC1") (pin "1") (pinfunction "+IN_1") (pintype "input"))
      (node (ref "R6") (pin "2") (pinfunction "2_2") (pintype "passive"))
      (node (ref "R7") (pin "1") (pinfunction "1_1") (pintype "passive"))
    )
    (net (code "47") (name "Net-(IC1--IN)") (class "Default")
      (node (ref "C6") (pin "+") (pinfunction "+_+") (pintype "passive"))
      (node (ref "IC1") (pin "2") (pinfunction "-IN_2") (pintype "input"))
      (node (ref "R8") (pin "1") (pinfunction "1_1") (pintype "passive"))
    )
    (net (code "48") (name "Net-(IC1-OUT)") (class "Default")
      (node (ref "IC1") (pin "4") (pinfunction "OUT_4") (pintype "output"))
      (node (ref "K2") (pin "S2") (pinfunction "S_S2") (pintype "passive"))
      (node (ref "R30") (pin "1") (pinfunction "1_1") (pintype "passive"))
      (node (ref "R8") (pin "2") (pinfunction "2_2") (pintype "passive"))
    )
    (net (code "49") (name "Net-(IC2-+IN)") (class "Default")
      (node (ref "IC2") (pin "1") (pinfunction "+IN_1") (pintype "input"))
      (node (ref "R16") (pin "2") (pinfunction "2_2") (pintype "passive"))
      (node (ref "R17") (pin "1") (pinfunction "1_1") (pintype "passive"))
    )
    (net (code "50") (name "Net-(IC2--IN)") (class "Default")
      (node (ref "C8") (pin "+") (pinfunction "+_+") (pintype "passive"))
      (node (ref "IC2") (pin "2") (pinfunction "-IN_2") (pintype "input"))
      (node (ref "R19") (pin "1") (pinfunction "1_1") (pintype "passive"))
    )
    (net (code "51") (name "Net-(IC2-OUT)") (class "Default")
      (node (ref "IC2") (pin "4") (pinfunction "OUT_4") (pintype "output"))
      (node (ref "K2") (pin "S1") (pinfunction "S_S1") (pintype "passive"))
      (node (ref "R19") (pin "2") (pinfunction "2_2") (pintype "passive"))
      (node (ref "R31") (pin "1") (pinfunction "1_1") (pintype "passive"))
    )
    (net (code "52") (name "Net-(IC3-+IN)") (class "Default")
      (node (ref "IC3") (pin "1") (pinfunction "+IN_1") (pintype "input"))
      (node (ref "R22") (pin "2") (pinfunction "2_2") (pintype "passive"))
      (node (ref "R23") (pin "1") (pinfunction "1_1") (pintype "passive"))
    )
    (net (code "53") (name "Net-(IC3--IN)") (class "Default")
      (node (ref "C16") (pin "+") (pinfunction "+_+") (pintype "passive"))
      (node (ref "IC3") (pin "2") (pinfunction "-IN_2") (pintype "input"))
      (node (ref "R26") (pin "1") (pinfunction "1_1") (pintype "passive"))
    )
    (net (code "54") (name "Net-(IC3-OUT)") (class "Default")
      (node (ref "IC3") (pin "4") (pinfunction "OUT_4") (pintype "output"))
      (node (ref "K1") (pin "S2") (pinfunction "S_S2") (pintype "passive"))
      (node (ref "R26") (pin "2") (pinfunction "2_2") (pintype "passive"))
      (node (ref "R39") (pin "1") (pinfunction "1_1") (pintype "passive"))
    )
    (net (code "55") (name "Net-(IC4-+IN)") (class "Default")
      (node (ref "IC4") (pin "1") (pinfunction "+IN_1") (pintype "input"))
      (node (ref "R33") (pin "2") (pinfunction "2_2") (pintype "passive"))
      (node (ref "R34") (pin "1") (pinfunction "1_1") (pintype "passive"))
    )
    (net (code "56") (name "Net-(IC4--IN)") (class "Default")
      (node (ref "C19") (pin "+") (pinfunction "+_+") (pintype "passive"))
      (node (ref "IC4") (pin "2") (pinfunction "-IN_2") (pintype "input"))
      (node (ref "R36") (pin "1") (pinfunction "1_1") (pintype "passive"))
    )
    (net (code "57") (name "Net-(IC4-OUT)") (class "Default")
      (node (ref "IC4") (pin "4") (pinfunction "OUT_4") (pintype "output"))
      (node (ref "K1") (pin "S1") (pinfunction "S_S1") (pintype "passive"))
      (node (ref "R36") (pin "2") (pinfunction "2_2") (pintype "passive"))
      (node (ref "R38") (pin "1") (pinfunction "1_1") (pintype "passive"))
    )
    (net (code "58") (name "Net-(IC5A--IN)") (class "Default")
      (node (ref "IC5") (pin "2") (pinfunction "-IN_2") (pintype "input"))
      (node (ref "R43") (pin "2") (pinfunction "2_2") (pintype "passive"))
      (node (ref "R44") (pin "2") (pinfunction "2_2") (pintype "passive"))
    )
    (net (code "59") (name "Net-(IC5A-OUT)") (class "Default")
      (node (ref "IC5") (pin "1") (pinfunction "OUT_1") (pintype "output"))
      (node (ref "R44") (pin "1") (pinfunction "1_1") (pintype "passive"))
      (node (ref "R45") (pin "2") (pinfunction "2_2") (pintype "passive"))
    )
    (net (code "60") (name "Net-(IC6A--IN)") (class "Default")
      (node (ref "IC6") (pin "2") (pinfunction "-IN_2") (pintype "input"))
      (node (ref "R20") (pin "2") (pinfunction "2_2") (pintype "passive"))
      (node (ref "R32") (pin "2") (pinfunction "2_2") (pintype "passive"))
    )
    (net (code "61") (name "Net-(IC6A-OUT)") (class "Default")
      (node (ref "IC6") (pin "1") (pinfunction "OUT_1") (pintype "output"))
      (node (ref "R32") (pin "1") (pinfunction "1_1") (pintype "passive"))
      (node (ref "R37") (pin "2") (pinfunction "2_2") (pintype "passive"))
    )
    (net (code "62") (name "Net-(K1B-P)") (class "Default")
      (node (ref "J3") (pin "1") (pinfunction "1_1") (pintype "passive"))
      (node (ref "K1") (pin "P1") (pinfunction "P_P1") (pintype "passive"))
    )
    (net (code "63") (name "Net-(K1C-P)") (class "Default")
      (node (ref "J3") (pin "3") (pinfunction "3_3") (pintype "passive"))
      (node (ref "K1") (pin "P2") (pinfunction "P_P2") (pintype "passive"))
    )
    (net (code "64") (name "Net-(K2B-P)") (class "Default")
      (node (ref "J6") (pin "1") (pinfunction "1_1") (pintype "passive"))
      (node (ref "K2") (pin "P1") (pinfunction "P_P1") (pintype "passive"))
    )
    (net (code "65") (name "Net-(K2C-P)") (class "Default")
      (node (ref "J6") (pin "3") (pinfunction "3_3") (pintype "passive"))
      (node (ref "K2") (pin "P2") (pinfunction "P_P2") (pintype "passive"))
    )
    (net (code "66") (name "Net-(R21-A)") (class "Default")
      (node (ref "R21") (pin "1") (pinfunction "A_1") (pintype "passive"))
      (node (ref "R29") (pin "1") (pinfunction "1_1") (pintype "passive"))
    )
    (net (code "67") (name "Net-(R21-S)") (class "Default")
      (node (ref "C10") (pin "1") (pinfunction "1_1") (pintype "bidirectional"))
      (node (ref "R21") (pin "2") (pinfunction "S_2") (pintype "passive"))
      (node (ref "U2") (pin "7") (pinfunction "7_7") (pintype "bidirectional"))
    )
    (net (code "68") (name "Net-(R27-Pad2)") (class "Default")
      (node (ref "R27") (pin "2") (pinfunction "2_2") (pintype "passive"))
      (node (ref "R29") (pin "2") (pinfunction "2_2") (pintype "passive"))
      (node (ref "U2") (pin "8") (pinfunction "8_8") (pintype "bidirectional"))
    )
    (net (code "69") (name "Net-(W01A-E)") (class "Default")
      (node (ref "R1") (pin "2") (pinfunction "2_2") (pintype "passive"))
      (node (ref "W01") (pin "1-3") (pinfunction "E_1-3") (pintype "passive"))
    )
    (net (code "70") (name "Net-(W01B-E)") (class "Default")
      (node (ref "R11") (pin "2") (pinfunction "2_2") (pintype "passive"))
      (node (ref "W01") (pin "2-3") (pinfunction "E_2-3") (pintype "passive"))
    )
    (net (code "71") (name "Net-(W03A-S)") (class "Default")
      (node (ref "R4") (pin "2") (pinfunction "2_2") (pintype "passive"))
      (node (ref "R5") (pin "2") (pinfunction "2_2") (pintype "passive"))
      (node (ref "W03") (pin "1-2") (pinfunction "S_1-2") (pintype "passive"))
    )
    (net (code "72") (name "Net-(W03B-S)") (class "Default")
      (node (ref "R14") (pin "2") (pinfunction "2_2") (pintype "passive"))
      (node (ref "R15") (pin "2") (pinfunction "2_2") (pintype "passive"))
      (node (ref "W03") (pin "2-2") (pinfunction "S_2-2") (pintype "passive"))
    )
    (net (code "73") (name "Net-(W04A-S)") (class "Default")
      (node (ref "R33") (pin "1") (pinfunction "1_1") (pintype "passive"))
      (node (ref "W04") (pin "1-2") (pinfunction "S_1-2") (pintype "passive"))
    )
    (net (code "74") (name "Net-(W04B-S)") (class "Default")
      (node (ref "R22") (pin "1") (pinfunction "1_1") (pintype "passive"))
      (node (ref "W04") (pin "2-2") (pinfunction "S_2-2") (pintype "passive"))
    )
    (net (code "75") (name "SUPPLY0_GND_") (class "Default")
      (node (ref "C17") (pin "P$1") (pinfunction "2_P$1") (pintype "bidirectional"))
      (node (ref "C22") (pin "P$2") (pinfunction "1_P$2") (pintype "bidirectional"))
      (node (ref "C23") (pin "P$2") (pinfunction "1_P$2") (pintype "bidirectional"))
      (node (ref "C27") (pin "P$1") (pinfunction "2_P$1") (pintype "bidirectional"))
      (node (ref "C30") (pin "P$2") (pinfunction "1_P$2") (pintype "bidirectional"))
      (node (ref "C4") (pin "P$2") (pinfunction "1_P$2") (pintype "bidirectional"))
      (node (ref "J1") (pin "2") (pinfunction "2_2") (pintype "passive"))
      (node (ref "J2") (pin "2") (pinfunction "2_2") (pintype "passive"))
      (node (ref "J3") (pin "2") (pinfunction "2_2") (pintype "passive"))
      (node (ref "J4") (pin "2") (pinfunction "2_2") (pintype "passive"))
      (node (ref "J6") (pin "2") (pinfunction "2_2") (pintype "passive"))
      (node (ref "J7") (pin "2") (pinfunction "2_2") (pintype "passive"))
      (node (ref "R10") (pin "1") (pinfunction "1_1") (pintype "passive"))
      (node (ref "R13") (pin "1") (pinfunction "1_1") (pintype "passive"))
      (node (ref "R17") (pin "2") (pinfunction "2_2") (pintype "passive"))
      (node (ref "R18") (pin "1") (pinfunction "1_1") (pintype "passive"))
      (node (ref "R20") (pin "1") (pinfunction "1_1") (pintype "passive"))
      (node (ref "R23") (pin "2") (pinfunction "2_2") (pintype "passive"))
      (node (ref "R24") (pin "1") (pinfunction "1_1") (pintype "passive"))
      (node (ref "R3") (pin "1") (pinfunction "1_1") (pintype "passive"))
      (node (ref "R34") (pin "2") (pinfunction "2_2") (pintype "passive"))
      (node (ref "R35") (pin "1") (pinfunction "1_1") (pintype "passive"))
      (node (ref "R42") (pin "1") (pinfunction "1_1") (pintype "passive"))
      (node (ref "R43") (pin "1") (pinfunction "1_1") (pintype "passive"))
      (node (ref "R7") (pin "2") (pinfunction "2_2") (pintype "passive"))
      (node (ref "R9") (pin "1") (pinfunction "1_1") (pintype "passive"))
      (node (ref "W01") (pin "1-1") (pinfunction "A_1-1") (pintype "passive"))
      (node (ref "W01") (pin "2-1") (pinfunction "A_2-1") (pintype "passive"))
      (node (ref "W04") (pin "1-1") (pinfunction "A_1-1") (pintype "passive"))
      (node (ref "W04") (pin "2-1") (pinfunction "A_2-1") (pintype "passive"))
    )
    (net (code "76") (name "unconnected-(R21-E-Pad3)") (class "Default")
      (node (ref "R21") (pin "3") (pinfunction "E_3") (pintype "passive"))
    )
  )
)
